# LipSync_Interface_Board.net
KiCad netlist of a schematic drawn in EAGLE
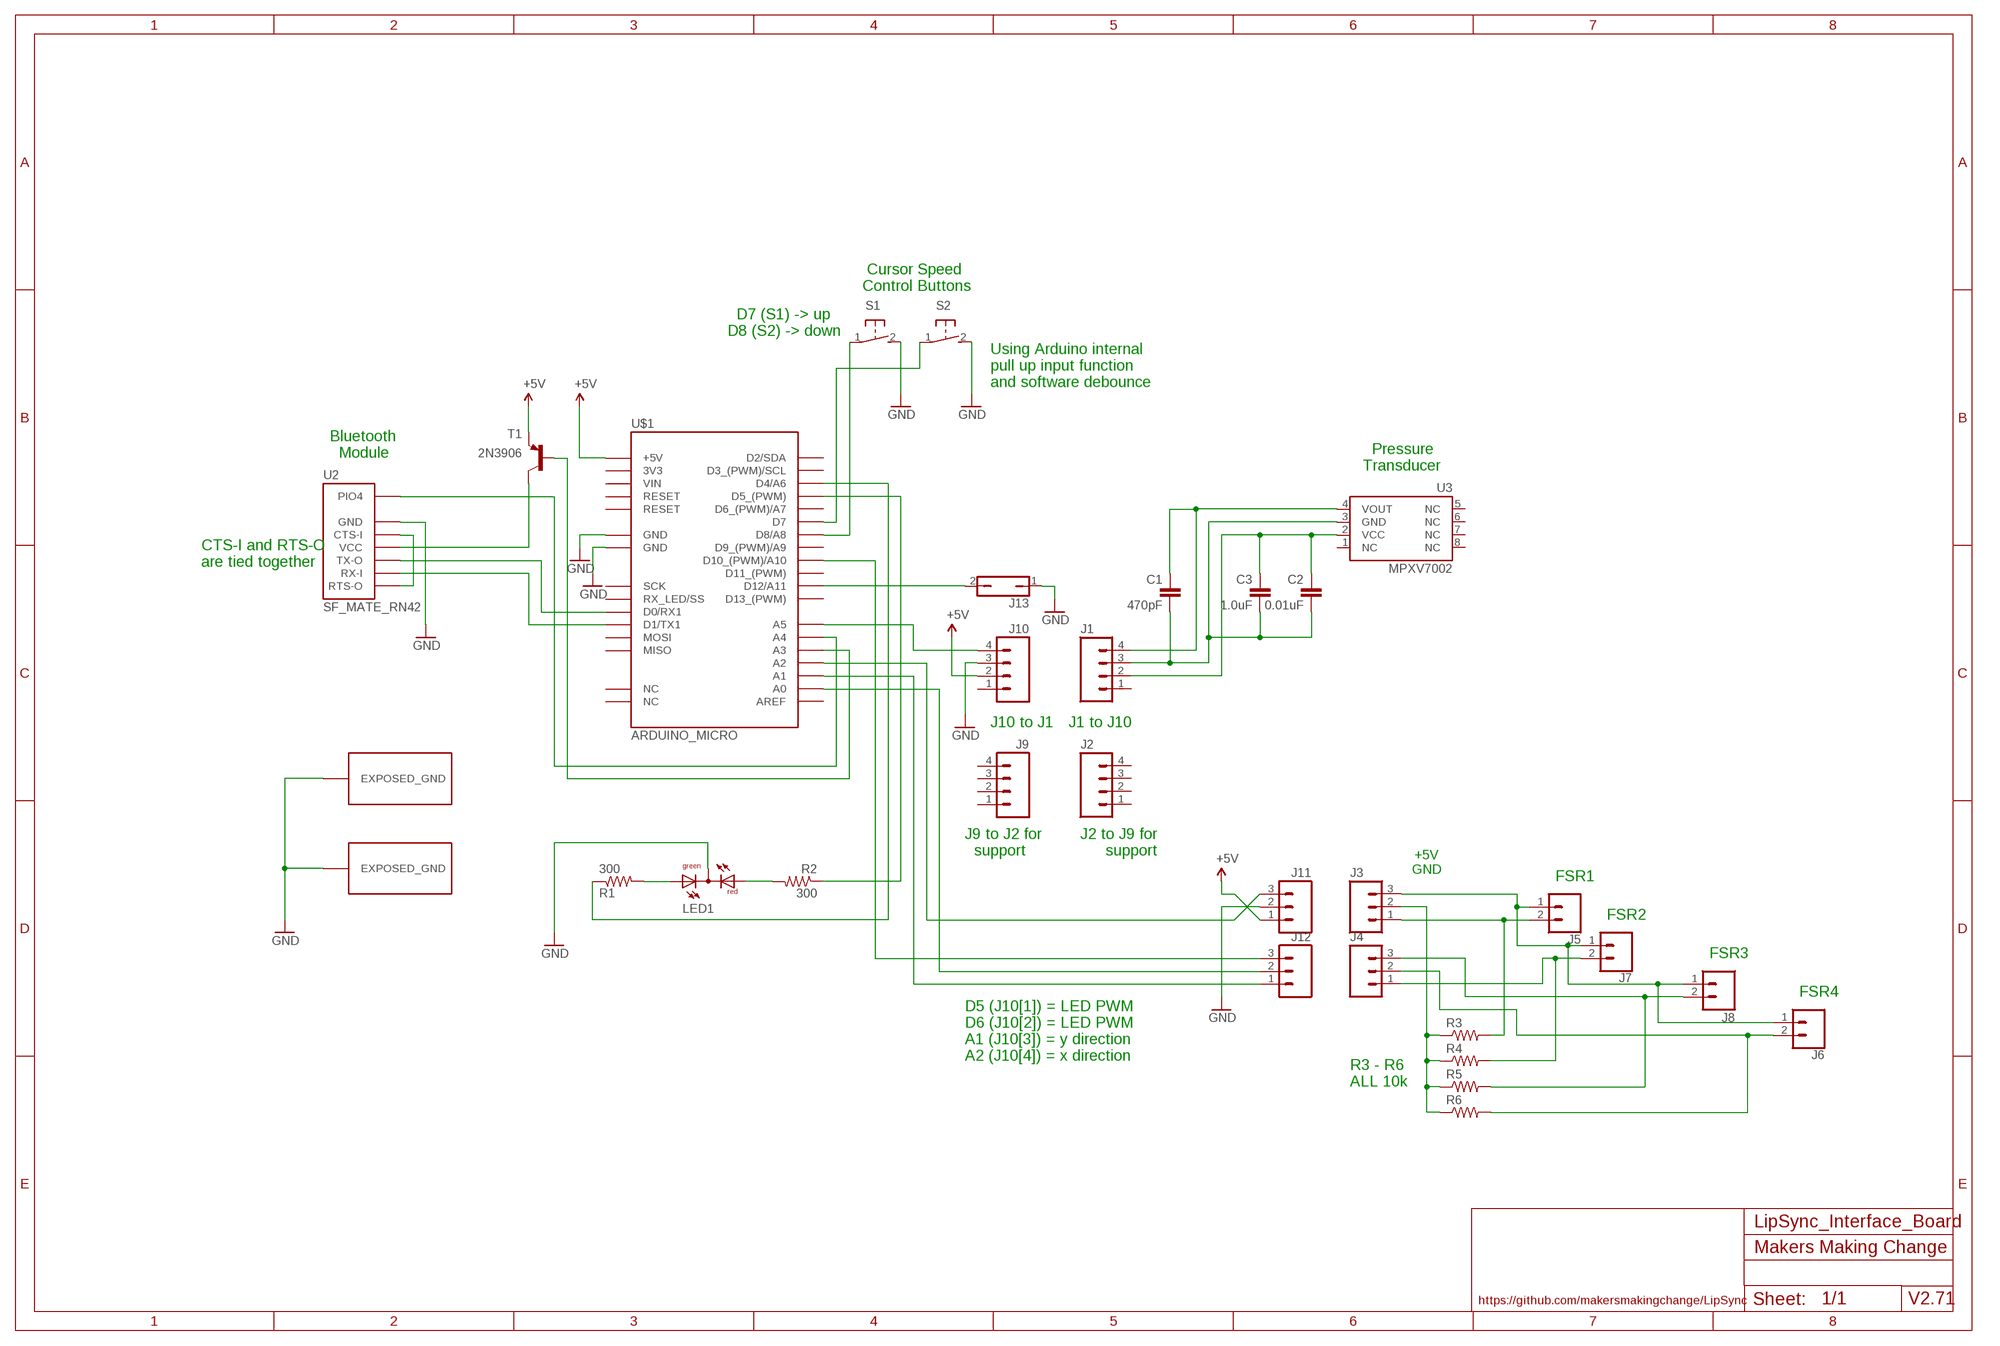
[diagram p0: schematic, sheet 1]

(export (version "E")
  (design (tool "Eeschema 10.0.6"))
  (components
    (comp (ref "C1")
      (value "470pF")
      (footprint "eagle-import:CAP-PTH-SMALLEZ")
      (libsource (lib "eagle-import") (part "CAPEZ"))
    )
    (comp (ref "C2")
      (value "0.01uF")
      (footprint "eagle-import:CAP-PTH-SMALLEZ")
      (libsource (lib "eagle-import") (part "CAPEZ"))
    )
    (comp (ref "C3")
      (value "1.0uF")
      (footprint "eagle-import:CAP-PTH-SMALLEZ")
      (libsource (lib "eagle-import") (part "CAPEZ"))
    )
    (comp (ref "J1")
      (value "M04PTH")
      (footprint "eagle-import:1X04")
      (libsource (lib "eagle-import") (part "M04PTH"))
    )
    (comp (ref "J2")
      (value "M04PTH")
      (footprint "eagle-import:1X04")
      (libsource (lib "eagle-import") (part "M04PTH"))
    )
    (comp (ref "J3")
      (value "M03LOCK")
      (footprint "eagle-import:1X03_LOCK")
      (libsource (lib "eagle-import") (part "M03LOCK"))
    )
    (comp (ref "J4")
      (value "M03LOCK")
      (footprint "eagle-import:1X03_LOCK")
      (libsource (lib "eagle-import") (part "M03LOCK"))
    )
    (comp (ref "J5")
      (value "CONN_02PTH3")
      (footprint "eagle-import:1X02_LONGPADS")
      (libsource (lib "eagle-import") (part "CONN_02PTH3"))
    )
    (comp (ref "J6")
      (value "CONN_02PTH3")
      (footprint "eagle-import:1X02_LONGPADS")
      (libsource (lib "eagle-import") (part "CONN_02PTH3"))
    )
    (comp (ref "J7")
      (value "CONN_02PTH3")
      (footprint "eagle-import:1X02_LONGPADS")
      (libsource (lib "eagle-import") (part "CONN_02PTH3"))
    )
    (comp (ref "J8")
      (value "M02PTH3")
      (footprint "eagle-import:1X02_LONGPADS@1")
      (libsource (lib "eagle-import") (part "M02PTH3"))
    )
    (comp (ref "J9")
      (value "M04PTH")
      (footprint "eagle-import:1X04")
      (libsource (lib "eagle-import") (part "M04PTH"))
    )
    (comp (ref "J10")
      (value "M04PTH")
      (footprint "eagle-import:1X04")
      (libsource (lib "eagle-import") (part "M04PTH"))
    )
    (comp (ref "J11")
      (value "M03LOCK")
      (footprint "eagle-import:1X03_LOCK")
      (libsource (lib "eagle-import") (part "M03LOCK"))
    )
    (comp (ref "J12")
      (value "M03LOCK")
      (footprint "eagle-import:1X03_LOCK")
      (libsource (lib "eagle-import") (part "M03LOCK"))
    )
    (comp (ref "J13")
      (value "JP1Q")
      (footprint "eagle-import:JP1")
      (libsource (lib "eagle-import") (part "JP1Q"))
    )
    (comp (ref "LED1")
      (value "DUOLED-RG-C")
      (footprint "eagle-import:DUOLED-C-5MM")
      (libsource (lib "eagle-import") (part "DUOLED-RG-C"))
    )
    (comp (ref "R1")
      (value "300")
      (footprint "eagle-import:AXIAL-0.3")
      (libsource (lib "eagle-import") (part "RESISTORAXIAL-0.3"))
    )
    (comp (ref "R2")
      (value "300")
      (footprint "eagle-import:AXIAL-0.3")
      (libsource (lib "eagle-import") (part "RESISTORAXIAL-0.3"))
    )
    (comp (ref "R3")
      (value "R-US_0204/5")
      (footprint "eagle-import:0204_5")
      (libsource (lib "eagle-import") (part "R-US_0204/5"))
    )
    (comp (ref "R4")
      (value "R-US_0204/5")
      (footprint "eagle-import:0204_5")
      (libsource (lib "eagle-import") (part "R-US_0204/5"))
    )
    (comp (ref "R5")
      (value "R-US_0204/5")
      (footprint "eagle-import:0204_5")
      (libsource (lib "eagle-import") (part "R-US_0204/5"))
    )
    (comp (ref "R6")
      (value "R-US_0204/5")
      (footprint "eagle-import:0204_5")
      (libsource (lib "eagle-import") (part "R-US_0204/5"))
    )
    (comp (ref "S1")
      (value "31-XXB3F-31XX-CUSTOM")
      (footprint "eagle-import:B3F-31XX-CUSTOM")
      (libsource (lib "eagle-import") (part "31-XXB3F-31XX-CUSTOM"))
    )
    (comp (ref "S2")
      (value "31-XXB3F-31XX-CUSTOM")
      (footprint "eagle-import:B3F-31XX-CUSTOM")
      (libsource (lib "eagle-import") (part "31-XXB3F-31XX-CUSTOM"))
    )
    (comp (ref "T1")
      (value "2N3906")
      (footprint "eagle-import:TO92-EBC")
      (libsource (lib "eagle-import") (part "-PNP-TO92-EBC2N3906"))
    )
    (comp (ref "U$1")
      (value "ARDUINO_MICRO")
      (footprint "eagle-import:ARDUINO_MICRO_HEADER_FOOTPRINT")
      (libsource (lib "eagle-import") (part "ARDUINO_MICRO"))
    )
    (comp (ref "U$2")
      (value "EXPOSED_GND")
      (footprint "eagle-import:EXPOSED_GND")
      (libsource (lib "eagle-import") (part "EXPOSED_GND"))
    )
    (comp (ref "U$3")
      (value "EXPOSED_GND")
      (footprint "eagle-import:EXPOSED_GND")
      (libsource (lib "eagle-import") (part "EXPOSED_GND"))
    )
    (comp (ref "U2")
      (value "SF_MATE_RN42")
      (footprint "eagle-import:BLUE_MATE_RN42_HEADER_FOOTPRINT")
      (libsource (lib "eagle-import") (part "SF_MATE_RN42"))
    )
    (comp (ref "U3")
      (value "MPXV7002")
      (footprint "eagle-import:SOP8")
      (libsource (lib "eagle-import") (part "MPXV7002"))
    )
  )
  (nets
    (net (code "1") (name "+5V") (class "Default")
      (node (ref "J10") (pin "2") (pinfunction "2_2") (pintype "passive"))
      (node (ref "J11") (pin "1") (pinfunction "1_1") (pintype "passive"))
      (node (ref "T1") (pin "E") (pinfunction "E_E") (pintype "passive"))
      (node (ref "U$1") (pin "5V") (pinfunction "+5V_5V") (pintype "power_in"))
    )
    (net (code "2") (name "/3V3") (class "Default")
      (node (ref "U$1") (pin "3V3") (pinfunction "3V3_3V3") (pintype "power_in"))
    )
    (net (code "3") (name "EXPOSED_GND") (class "Default")
      (node (ref "J10") (pin "3") (pinfunction "3_3") (pintype "passive"))
      (node (ref "J11") (pin "2") (pinfunction "2_2") (pintype "passive"))
      (node (ref "J13") (pin "1") (pinfunction "1_1") (pintype "passive"))
      (node (ref "LED1") (pin "C") (pinfunction "C_C") (pintype "passive"))
      (node (ref "S1") (pin "2") (pinfunction "S_2") (pintype "passive"))
      (node (ref "S2") (pin "2") (pinfunction "S_2") (pintype "passive"))
      (node (ref "U$1") (pin "GND") (pinfunction "GND_GND") (pintype "power_in"))
      (node (ref "U$1") (pin "GND@1") (pinfunction "GND_GND@1") (pintype "power_in"))
      (node (ref "U$2") (pin "GND1") (pinfunction "EXPOSED_GND_GND1") (pintype "power_in"))
      (node (ref "U$3") (pin "GND1") (pinfunction "EXPOSED_GND_GND1") (pintype "power_in"))
      (node (ref "U2") (pin "GND") (pinfunction "GND_GND") (pintype "power_in"))
    )
    (net (code "4") (name "Net-(J3-Pad1)") (class "Default")
      (node (ref "J3") (pin "1") (pinfunction "1_1") (pintype "passive"))
      (node (ref "J5") (pin "2") (pinfunction "2_2") (pintype "passive"))
      (node (ref "R3") (pin "2") (pinfunction "2_2") (pintype "passive"))
    )
    (net (code "5") (name "Net-(J3-Pad2)") (class "Default")
      (node (ref "J3") (pin "2") (pinfunction "2_2") (pintype "passive"))
      (node (ref "R3") (pin "1") (pinfunction "1_1") (pintype "passive"))
      (node (ref "R4") (pin "1") (pinfunction "1_1") (pintype "passive"))
      (node (ref "R5") (pin "1") (pinfunction "1_1") (pintype "passive"))
      (node (ref "R6") (pin "1") (pinfunction "1_1") (pintype "passive"))
    )
    (net (code "6") (name "Net-(J3-Pad3)") (class "Default")
      (node (ref "J3") (pin "3") (pinfunction "3_3") (pintype "passive"))
      (node (ref "J5") (pin "1") (pinfunction "1_1") (pintype "passive"))
      (node (ref "J6") (pin "1") (pinfunction "1_1") (pintype "passive"))
      (node (ref "J7") (pin "1") (pinfunction "1_1") (pintype "passive"))
      (node (ref "J8") (pin "1") (pinfunction "1_1") (pintype "passive"))
    )
    (net (code "7") (name "Net-(J4-Pad1)") (class "Default")
      (node (ref "J4") (pin "1") (pinfunction "1_1") (pintype "passive"))
      (node (ref "J7") (pin "2") (pinfunction "2_2") (pintype "passive"))
      (node (ref "R4") (pin "2") (pinfunction "2_2") (pintype "passive"))
    )
    (net (code "8") (name "Net-(J4-Pad2)") (class "Default")
      (node (ref "J4") (pin "2") (pinfunction "2_2") (pintype "passive"))
      (node (ref "J6") (pin "2") (pinfunction "2_2") (pintype "passive"))
      (node (ref "R6") (pin "2") (pinfunction "2_2") (pintype "passive"))
    )
    (net (code "9") (name "Net-(J4-Pad3)") (class "Default")
      (node (ref "J4") (pin "3") (pinfunction "3_3") (pintype "passive"))
      (node (ref "J8") (pin "2") (pinfunction "2_2") (pintype "passive"))
      (node (ref "R5") (pin "2") (pinfunction "2_2") (pintype "passive"))
    )
    (net (code "10") (name "Net-(J10-Pad4)") (class "Default")
      (node (ref "J10") (pin "4") (pinfunction "4_4") (pintype "passive"))
      (node (ref "U$1") (pin "A5") (pinfunction "A5_A5") (pintype "bidirectional"))
    )
    (net (code "11") (name "Net-(J11-Pad3)") (class "Default")
      (node (ref "J11") (pin "3") (pinfunction "3_3") (pintype "passive"))
      (node (ref "U$1") (pin "A2") (pinfunction "A2_A2") (pintype "bidirectional"))
    )
    (net (code "12") (name "Net-(J12-Pad1)") (class "Default")
      (node (ref "J12") (pin "1") (pinfunction "1_1") (pintype "passive"))
      (node (ref "U$1") (pin "A1") (pinfunction "A1_A1") (pintype "bidirectional"))
    )
    (net (code "13") (name "Net-(J12-Pad2)") (class "Default")
      (node (ref "J12") (pin "2") (pinfunction "2_2") (pintype "passive"))
      (node (ref "U$1") (pin "A0") (pinfunction "A0_A0") (pintype "bidirectional"))
    )
    (net (code "14") (name "Net-(LED1-AG)") (class "Default")
      (node (ref "LED1") (pin "AX") (pinfunction "AG_AX") (pintype "passive"))
      (node (ref "R1") (pin "P$2") (pinfunction "2_P$2") (pintype "passive"))
    )
    (net (code "15") (name "Net-(R1-1)") (class "Default")
      (node (ref "R1") (pin "P$1") (pinfunction "1_P$1") (pintype "passive"))
      (node (ref "U$1") (pin "D4") (pinfunction "D4/A6_D4") (pintype "bidirectional"))
    )
    (net (code "16") (name "Net-(R2-1)") (class "Default")
      (node (ref "R2") (pin "P$1") (pinfunction "1_P$1") (pintype "passive"))
      (node (ref "U$1") (pin "D5") (pinfunction "D5_(PWM)_D5") (pintype "bidirectional"))
    )
    (net (code "17") (name "Net-(R2-2)") (class "Default")
      (node (ref "LED1") (pin "AR") (pinfunction "AR_AR") (pintype "passive"))
      (node (ref "R2") (pin "P$2") (pinfunction "2_P$2") (pintype "passive"))
    )
    (net (code "18") (name "Net-(S1-P)") (class "Default")
      (node (ref "S1") (pin "1") (pinfunction "P_1") (pintype "passive"))
      (node (ref "U$1") (pin "D8") (pinfunction "D8/A8_D8") (pintype "bidirectional"))
    )
    (net (code "19") (name "Net-(S2-P)") (class "Default")
      (node (ref "S2") (pin "1") (pinfunction "P_1") (pintype "passive"))
      (node (ref "U$1") (pin "D7") (pinfunction "D7_D7") (pintype "bidirectional"))
    )
    (net (code "20") (name "Net-(T1-PadB)") (class "Default")
      (node (ref "T1") (pin "B") (pinfunction "B_B") (pintype "passive"))
      (node (ref "U$1") (pin "A3") (pinfunction "A3_A3") (pintype "bidirectional"))
    )
    (net (code "21") (name "Net-(T1-PadC)") (class "Default")
      (node (ref "T1") (pin "C") (pinfunction "C_C") (pintype "passive"))
      (node (ref "U2") (pin "VCC") (pinfunction "VCC_VCC") (pintype "power_in"))
    )
    (net (code "22") (name "Net-(U$1-D0{slash}RX1)") (class "Default")
      (node (ref "U$1") (pin "RX1") (pinfunction "D0/RX1_RX1") (pintype "input"))
      (node (ref "U2") (pin "TX-O") (pinfunction "TX-O_TX-O") (pintype "output"))
    )
    (net (code "23") (name "Net-(U$1-D1{slash}TX1)") (class "Default")
      (node (ref "U$1") (pin "TX1") (pinfunction "D1/TX1_TX1") (pintype "output"))
      (node (ref "U2") (pin "RX-I") (pinfunction "RX-I_RX-I") (pintype "input"))
    )
    (net (code "24") (name "Net-(U$1-D10_(PWM){slash}A10)") (class "Default")
      (node (ref "J12") (pin "3") (pinfunction "3_3") (pintype "passive"))
      (node (ref "U$1") (pin "D10") (pinfunction "D10_(PWM)/A10_D10") (pintype "bidirectional"))
    )
    (net (code "25") (name "Net-(U$1-D12{slash}A11)") (class "Default")
      (node (ref "J13") (pin "2") (pinfunction "2_2") (pintype "passive"))
      (node (ref "U$1") (pin "D12") (pinfunction "D12/A11_D12") (pintype "bidirectional"))
    )
    (net (code "26") (name "Net-(U$1-PadA4)") (class "Default")
      (node (ref "U$1") (pin "A4") (pinfunction "A4_A4") (pintype "bidirectional"))
      (node (ref "U2") (pin "PIO4") (pinfunction "PIO4_PIO4") (pintype "input"))
    )
    (net (code "27") (name "Net-(U2-PadCTS-I)") (class "Default")
      (node (ref "U2") (pin "CTS-I") (pinfunction "CTS-I_CTS-I") (pintype "input"))
      (node (ref "U2") (pin "RTS-O") (pinfunction "RTS-O_RTS-O") (pintype "output"))
    )
    (net (code "28") (name "Net-(U3-GND)") (class "Default")
      (node (ref "C1") (pin "2") (pinfunction "2_2") (pintype "passive"))
      (node (ref "C2") (pin "2") (pinfunction "2_2") (pintype "passive"))
      (node (ref "C3") (pin "2") (pinfunction "2_2") (pintype "passive"))
      (node (ref "J1") (pin "3") (pinfunction "3_3") (pintype "passive"))
      (node (ref "U3") (pin "3") (pinfunction "GND_3") (pintype "power_in"))
    )
    (net (code "29") (name "Net-(U3-VCC)") (class "Default")
      (node (ref "C2") (pin "1") (pinfunction "1_1") (pintype "passive"))
      (node (ref "C3") (pin "1") (pinfunction "1_1") (pintype "passive"))
      (node (ref "J1") (pin "2") (pinfunction "2_2") (pintype "passive"))
      (node (ref "U3") (pin "2") (pinfunction "VCC_2") (pintype "power_in"))
    )
    (net (code "30") (name "Net-(U3-VOUT)") (class "Default")
      (node (ref "C1") (pin "1") (pinfunction "1_1") (pintype "passive"))
      (node (ref "J1") (pin "4") (pinfunction "4_4") (pintype "passive"))
      (node (ref "U3") (pin "4") (pinfunction "VOUT_4") (pintype "output"))
    )
    (net (code "31") (name "unconnected-(J1-Pad1)") (class "Default")
      (node (ref "J1") (pin "1") (pinfunction "1_1") (pintype "passive"))
    )
    (net (code "32") (name "unconnected-(J2-Pad1)") (class "Default")
      (node (ref "J2") (pin "1") (pinfunction "1_1") (pintype "passive"))
    )
    (net (code "33") (name "unconnected-(J2-Pad2)") (class "Default")
      (node (ref "J2") (pin "2") (pinfunction "2_2") (pintype "passive"))
    )
    (net (code "34") (name "unconnected-(J2-Pad3)") (class "Default")
      (node (ref "J2") (pin "3") (pinfunction "3_3") (pintype "passive"))
    )
    (net (code "35") (name "unconnected-(J2-Pad4)") (class "Default")
      (node (ref "J2") (pin "4") (pinfunction "4_4") (pintype "passive"))
    )
    (net (code "36") (name "unconnected-(J9-Pad1)") (class "Default")
      (node (ref "J9") (pin "1") (pinfunction "1_1") (pintype "passive"))
    )
    (net (code "37") (name "unconnected-(J9-Pad2)") (class "Default")
      (node (ref "J9") (pin "2") (pinfunction "2_2") (pintype "passive"))
    )
    (net (code "38") (name "unconnected-(J9-Pad3)") (class "Default")
      (node (ref "J9") (pin "3") (pinfunction "3_3") (pintype "passive"))
    )
    (net (code "39") (name "unconnected-(J9-Pad4)") (class "Default")
      (node (ref "J9") (pin "4") (pinfunction "4_4") (pintype "passive"))
    )
    (net (code "40") (name "unconnected-(J10-Pad1)") (class "Default")
      (node (ref "J10") (pin "1") (pinfunction "1_1") (pintype "passive"))
    )
    (net (code "41") (name "unconnected-(U$1-AREF-PadREF)") (class "Default")
      (node (ref "U$1") (pin "REF") (pinfunction "AREF_REF") (pintype "input"))
    )
    (net (code "42") (name "unconnected-(U$1-D2{slash}SDA-PadD2)") (class "Default")
      (node (ref "U$1") (pin "D2") (pinfunction "D2/SDA_D2") (pintype "bidirectional"))
    )
    (net (code "43") (name "unconnected-(U$1-D3_(PWM){slash}SCL-PadD3)") (class "Default")
      (node (ref "U$1") (pin "D3") (pinfunction "D3_(PWM)/SCL_D3") (pintype "bidirectional"))
    )
    (net (code "44") (name "unconnected-(U$1-D6_(PWM){slash}A7-PadD6)") (class "Default")
      (node (ref "U$1") (pin "D6") (pinfunction "D6_(PWM)/A7_D6") (pintype "bidirectional"))
    )
    (net (code "45") (name "unconnected-(U$1-D9_(PWM){slash}A9-PadD9)") (class "Default")
      (node (ref "U$1") (pin "D9") (pinfunction "D9_(PWM)/A9_D9") (pintype "bidirectional"))
    )
    (net (code "46") (name "unconnected-(U$1-D11_(PWM)-PadD11)") (class "Default")
      (node (ref "U$1") (pin "D11") (pinfunction "D11_(PWM)_D11") (pintype "bidirectional"))
    )
    (net (code "47") (name "unconnected-(U$1-D13_(PWM)-PadD13)") (class "Default")
      (node (ref "U$1") (pin "D13") (pinfunction "D13_(PWM)_D13") (pintype "bidirectional"))
    )
    (net (code "48") (name "unconnected-(U$1-NC-PadNC@1)") (class "Default")
      (node (ref "U$1") (pin "NC@1") (pinfunction "NC_NC@1") (pintype "no_connect"))
    )
    (net (code "49") (name "unconnected-(U$1-PadMISO)") (class "Default")
      (node (ref "U$1") (pin "MISO") (pinfunction "MISO_MISO") (pintype "bidirectional"))
    )
    (net (code "50") (name "unconnected-(U$1-PadMOSI)") (class "Default")
      (node (ref "U$1") (pin "MOSI") (pinfunction "MOSI_MOSI") (pintype "bidirectional"))
    )
    (net (code "51") (name "unconnected-(U$1-PadNC)") (class "Default")
      (node (ref "U$1") (pin "NC") (pinfunction "NC_NC") (pintype "no_connect"))
    )
    (net (code "52") (name "unconnected-(U$1-PadSCK)") (class "Default")
      (node (ref "U$1") (pin "SCK") (pinfunction "SCK_SCK") (pintype "output"))
    )
    (net (code "53") (name "unconnected-(U$1-PadVIN)") (class "Default")
      (node (ref "U$1") (pin "VIN") (pinfunction "VIN_VIN") (pintype "input"))
    )
    (net (code "54") (name "unconnected-(U$1-RESET-PadRST)") (class "Default")
      (node (ref "U$1") (pin "RST") (pinfunction "RESET_RST") (pintype "input"))
    )
    (net (code "55") (name "unconnected-(U$1-RESET-PadRST@1)") (class "Default")
      (node (ref "U$1") (pin "RST@1") (pinfunction "RESET_RST@1") (pintype "input"))
    )
    (net (code "56") (name "unconnected-(U$1-RX_LED{slash}SS-PadSS)") (class "Default")
      (node (ref "U$1") (pin "SS") (pinfunction "RX_LED/SS_SS") (pintype "bidirectional"))
    )
    (net (code "57") (name "unconnected-(U3-NC-Pad1)") (class "Default")
      (node (ref "U3") (pin "1") (pinfunction "NC_1") (pintype "no_connect"))
    )
    (net (code "58") (name "unconnected-(U3-NC-Pad5)") (class "Default")
      (node (ref "U3") (pin "5") (pinfunction "NC_5") (pintype "no_connect"))
    )
    (net (code "59") (name "unconnected-(U3-NC-Pad6)") (class "Default")
      (node (ref "U3") (pin "6") (pinfunction "NC_6") (pintype "no_connect"))
    )
    (net (code "60") (name "unconnected-(U3-NC-Pad7)") (class "Default")
      (node (ref "U3") (pin "7") (pinfunction "NC_7") (pintype "no_connect"))
    )
    (net (code "61") (name "unconnected-(U3-NC-Pad8)") (class "Default")
      (node (ref "U3") (pin "8") (pinfunction "NC_8") (pintype "no_connect"))
    )
  )
)
